# jammasave.net
KiCad netlist of a schematic drawn in EAGLE
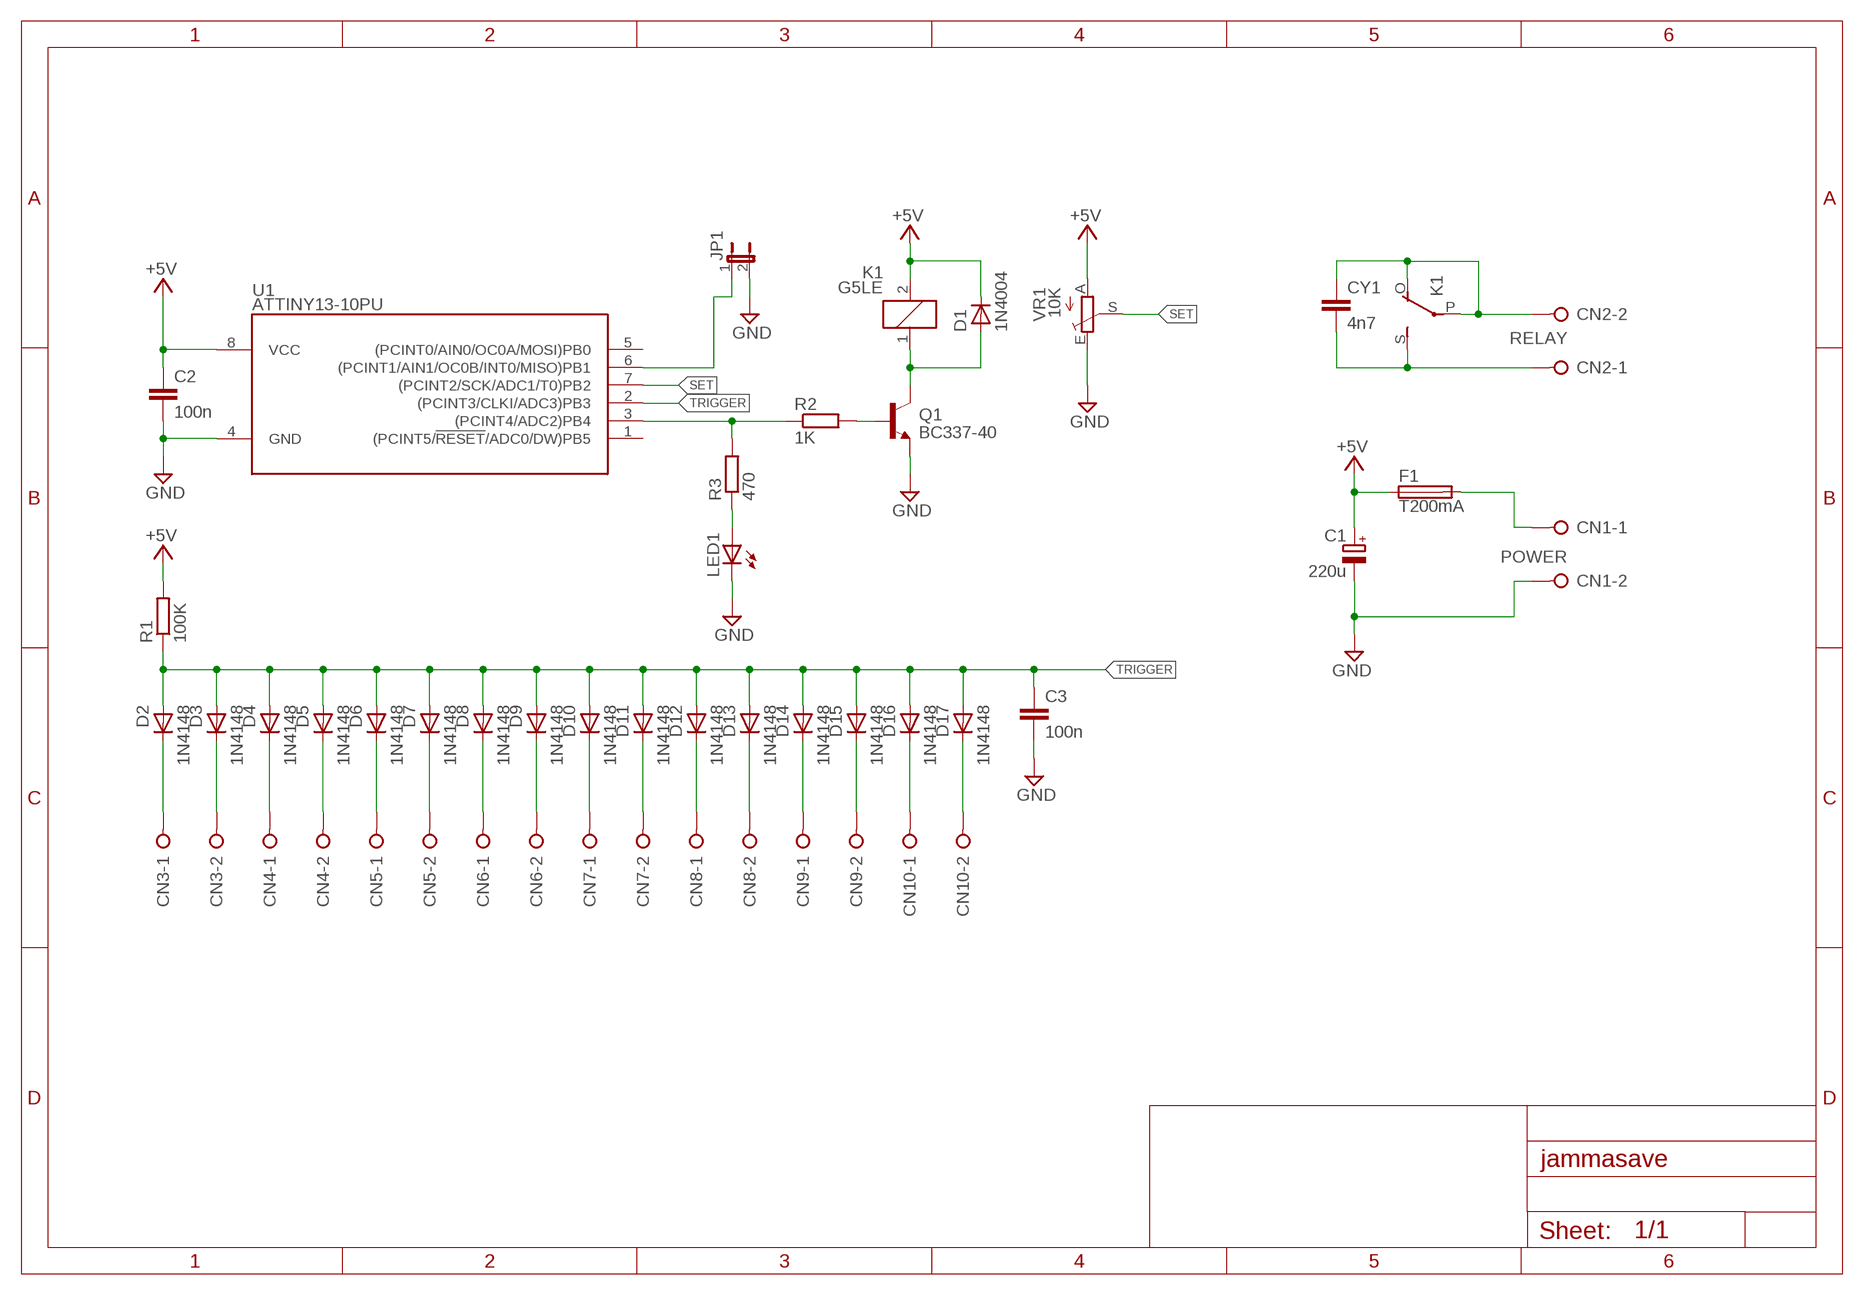
[diagram p0: schematic, sheet 1]

(export (version "E")
  (design (tool "Eeschema 10.0.6"))
  (components
    (comp (ref "C1")
      (value "220u")
      (footprint "eagle-import:E3,5-8")
      (libsource (lib "eagle-import") (part "CPOL-EUE3.5-8"))
    )
    (comp (ref "C2")
      (value "100n")
      (footprint "eagle-import:C050-035X075")
      (libsource (lib "eagle-import") (part "C-EU050-035X075"))
    )
    (comp (ref "C3")
      (value "100n")
      (footprint "eagle-import:C050-035X075")
      (libsource (lib "eagle-import") (part "C-EU050-035X075"))
    )
    (comp (ref "CN1")
      (value "POWER")
      (footprint "eagle-import:W237-132")
      (libsource (lib "eagle-import") (part "W237-02P"))
    )
    (comp (ref "CN2")
      (value "RELAY")
      (footprint "eagle-import:W237-2N")
      (libsource (lib "eagle-import") (part "W237-2N"))
    )
    (comp (ref "CN3")
      (value "W237-02P")
      (footprint "eagle-import:W237-132")
      (libsource (lib "eagle-import") (part "W237-02P"))
    )
    (comp (ref "CN4")
      (value "W237-02P")
      (footprint "eagle-import:W237-132")
      (libsource (lib "eagle-import") (part "W237-02P"))
    )
    (comp (ref "CN5")
      (value "W237-02P")
      (footprint "eagle-import:W237-132")
      (libsource (lib "eagle-import") (part "W237-02P"))
    )
    (comp (ref "CN6")
      (value "W237-02P")
      (footprint "eagle-import:W237-132")
      (libsource (lib "eagle-import") (part "W237-02P"))
    )
    (comp (ref "CN7")
      (value "W237-02P")
      (footprint "eagle-import:W237-132")
      (libsource (lib "eagle-import") (part "W237-02P"))
    )
    (comp (ref "CN8")
      (value "W237-02P")
      (footprint "eagle-import:W237-132")
      (libsource (lib "eagle-import") (part "W237-02P"))
    )
    (comp (ref "CN9")
      (value "W237-02P")
      (footprint "eagle-import:W237-132")
      (libsource (lib "eagle-import") (part "W237-02P"))
    )
    (comp (ref "CN10")
      (value "W237-02P")
      (footprint "eagle-import:W237-132")
      (libsource (lib "eagle-import") (part "W237-02P"))
    )
    (comp (ref "CY1")
      (value "4n7")
      (footprint "eagle-import:YC10B5")
      (libsource (lib "eagle-import") (part "CYYC10B5"))
    )
    (comp (ref "D1")
      (value "1N4004")
      (footprint "eagle-import:DO41-10")
      (libsource (lib "eagle-import") (part "-DIODE_?DO41-10"))
    )
    (comp (ref "D2")
      (value "1N4148")
      (footprint "eagle-import:DO35-7")
      (libsource (lib "eagle-import") (part "-DIODE_?DO35-7"))
    )
    (comp (ref "D3")
      (value "1N4148")
      (footprint "eagle-import:DO35-7")
      (libsource (lib "eagle-import") (part "-DIODE_?DO35-7"))
    )
    (comp (ref "D4")
      (value "1N4148")
      (footprint "eagle-import:DO35-7")
      (libsource (lib "eagle-import") (part "-DIODE_?DO35-7"))
    )
    (comp (ref "D5")
      (value "1N4148")
      (footprint "eagle-import:DO35-7")
      (libsource (lib "eagle-import") (part "-DIODE_?DO35-7"))
    )
    (comp (ref "D6")
      (value "1N4148")
      (footprint "eagle-import:DO35-7")
      (libsource (lib "eagle-import") (part "-DIODE_?DO35-7"))
    )
    (comp (ref "D7")
      (value "1N4148")
      (footprint "eagle-import:DO35-7")
      (libsource (lib "eagle-import") (part "-DIODE_?DO35-7"))
    )
    (comp (ref "D8")
      (value "1N4148")
      (footprint "eagle-import:DO35-7")
      (libsource (lib "eagle-import") (part "-DIODE_?DO35-7"))
    )
    (comp (ref "D9")
      (value "1N4148")
      (footprint "eagle-import:DO35-7")
      (libsource (lib "eagle-import") (part "-DIODE_?DO35-7"))
    )
    (comp (ref "D10")
      (value "1N4148")
      (footprint "eagle-import:DO35-7")
      (libsource (lib "eagle-import") (part "-DIODE_?DO35-7"))
    )
    (comp (ref "D11")
      (value "1N4148")
      (footprint "eagle-import:DO35-7")
      (libsource (lib "eagle-import") (part "-DIODE_?DO35-7"))
    )
    (comp (ref "D12")
      (value "1N4148")
      (footprint "eagle-import:DO35-7")
      (libsource (lib "eagle-import") (part "-DIODE_?DO35-7"))
    )
    (comp (ref "D13")
      (value "1N4148")
      (footprint "eagle-import:DO35-7")
      (libsource (lib "eagle-import") (part "-DIODE_?DO35-7"))
    )
    (comp (ref "D14")
      (value "1N4148")
      (footprint "eagle-import:DO35-7")
      (libsource (lib "eagle-import") (part "-DIODE_?DO35-7"))
    )
    (comp (ref "D15")
      (value "1N4148")
      (footprint "eagle-import:DO35-7")
      (libsource (lib "eagle-import") (part "-DIODE_?DO35-7"))
    )
    (comp (ref "D16")
      (value "1N4148")
      (footprint "eagle-import:DO35-7")
      (libsource (lib "eagle-import") (part "-DIODE_?DO35-7"))
    )
    (comp (ref "D17")
      (value "1N4148")
      (footprint "eagle-import:DO35-7")
      (libsource (lib "eagle-import") (part "-DIODE_?DO35-7"))
    )
    (comp (ref "F1")
      (value "T200mA")
      (footprint "eagle-import:TE5")
      (libsource (lib "eagle-import") (part "FUSETE5"))
    )
    (comp (ref "JP1")
      (value "JP1E")
      (footprint "eagle-import:JP1")
      (libsource (lib "eagle-import") (part "JP1E"))
    )
    (comp (ref "K1")
      (value "G5LE")
      (footprint "eagle-import:G5LE")
      (libsource (lib "eagle-import") (part "G5LE"))
    )
    (comp (ref "LED1")
      (value "LED3MM")
      (footprint "eagle-import:LED3MM")
      (libsource (lib "eagle-import") (part "LED3MM"))
    )
    (comp (ref "Q1")
      (value "BC337-40")
      (footprint "eagle-import:TO92-254")
      (libsource (lib "eagle-import") (part "-NPN_?TO92_254-CBE"))
    )
    (comp (ref "R1")
      (value "100K")
      (footprint "eagle-import:0207_10")
      (libsource (lib "eagle-import") (part "R-EU_0207/10"))
    )
    (comp (ref "R2")
      (value "1K")
      (footprint "eagle-import:0207_10")
      (libsource (lib "eagle-import") (part "R-EU_0207/10"))
    )
    (comp (ref "R3")
      (value "470")
      (footprint "eagle-import:0207_10")
      (libsource (lib "eagle-import") (part "R-EU_0207/10"))
    )
    (comp (ref "U1")
      (value "ATTINY13-10PU")
      (footprint "eagle-import:DIL08")
      (libsource (lib "eagle-import") (part "ATTINY13-PU10"))
    )
    (comp (ref "VR1")
      (value "10K")
      (footprint "eagle-import:CA6V")
      (libsource (lib "eagle-import") (part "TRIM_EU-CA6V"))
    )
  )
  (nets
    (net (code "1") (name "+5V") (class "Default")
      (node (ref "C1") (pin "+") (pinfunction "+_+") (pintype "passive"))
      (node (ref "C2") (pin "1") (pinfunction "1_1") (pintype "passive"))
      (node (ref "D1") (pin "K") (pinfunction "C_K") (pintype "passive"))
      (node (ref "F1") (pin "1") (pinfunction "1_1") (pintype "passive"))
      (node (ref "K1") (pin "2") (pinfunction "2_2") (pintype "passive"))
      (node (ref "R1") (pin "2") (pinfunction "2_2") (pintype "passive"))
      (node (ref "U1") (pin "8") (pinfunction "VCC_8") (pintype "power_in"))
      (node (ref "VR1") (pin "A") (pinfunction "A_A") (pintype "passive"))
    )
    (net (code "2") (name "GND") (class "Default")
      (node (ref "C1") (pin "-") (pinfunction "-_-") (pintype "passive"))
      (node (ref "C2") (pin "2") (pinfunction "2_2") (pintype "passive"))
      (node (ref "C3") (pin "2") (pinfunction "2_2") (pintype "passive"))
      (node (ref "CN1") (pin "2") (pinfunction "KL_2") (pintype "passive"))
      (node (ref "JP1") (pin "2") (pinfunction "2_2") (pintype "passive"))
      (node (ref "LED1") (pin "K") (pinfunction "C_K") (pintype "passive"))
      (node (ref "Q1") (pin "3") (pinfunction "E_3") (pintype "passive"))
      (node (ref "U1") (pin "4") (pinfunction "GND_4") (pintype "power_in"))
      (node (ref "VR1") (pin "E") (pinfunction "E_E") (pintype "passive"))
    )
    (net (code "3") (name "Net-(CN1A-KL)") (class "Default")
      (node (ref "CN1") (pin "1") (pinfunction "KL_1") (pintype "passive"))
      (node (ref "F1") (pin "2") (pinfunction "2_2") (pintype "passive"))
    )
    (net (code "4") (name "Net-(CN2A-KL)") (class "Default")
      (node (ref "CN2") (pin "1") (pinfunction "KL_1") (pintype "passive"))
      (node (ref "CY1") (pin "2") (pinfunction "2_2") (pintype "passive"))
      (node (ref "K1") (pin "S") (pinfunction "S_S") (pintype "passive"))
    )
    (net (code "5") (name "Net-(CN2B-KL)") (class "Default")
      (node (ref "CN2") (pin "2") (pinfunction "KL_2") (pintype "passive"))
      (node (ref "CY1") (pin "1") (pinfunction "1_1") (pintype "passive"))
      (node (ref "K1") (pin "O") (pinfunction "O_O") (pintype "passive"))
      (node (ref "K1") (pin "P") (pinfunction "P_P") (pintype "passive"))
    )
    (net (code "6") (name "Net-(CN3A-KL)") (class "Default")
      (node (ref "CN3") (pin "1") (pinfunction "KL_1") (pintype "passive"))
      (node (ref "D2") (pin "K") (pinfunction "C_K") (pintype "passive"))
    )
    (net (code "7") (name "Net-(CN3B-KL)") (class "Default")
      (node (ref "CN3") (pin "2") (pinfunction "KL_2") (pintype "passive"))
      (node (ref "D3") (pin "K") (pinfunction "C_K") (pintype "passive"))
    )
    (net (code "8") (name "Net-(CN4A-KL)") (class "Default")
      (node (ref "CN4") (pin "1") (pinfunction "KL_1") (pintype "passive"))
      (node (ref "D4") (pin "K") (pinfunction "C_K") (pintype "passive"))
    )
    (net (code "9") (name "Net-(CN4B-KL)") (class "Default")
      (node (ref "CN4") (pin "2") (pinfunction "KL_2") (pintype "passive"))
      (node (ref "D5") (pin "K") (pinfunction "C_K") (pintype "passive"))
    )
    (net (code "10") (name "Net-(CN5A-KL)") (class "Default")
      (node (ref "CN5") (pin "1") (pinfunction "KL_1") (pintype "passive"))
      (node (ref "D6") (pin "K") (pinfunction "C_K") (pintype "passive"))
    )
    (net (code "11") (name "Net-(CN5B-KL)") (class "Default")
      (node (ref "CN5") (pin "2") (pinfunction "KL_2") (pintype "passive"))
      (node (ref "D7") (pin "K") (pinfunction "C_K") (pintype "passive"))
    )
    (net (code "12") (name "Net-(CN6A-KL)") (class "Default")
      (node (ref "CN6") (pin "1") (pinfunction "KL_1") (pintype "passive"))
      (node (ref "D8") (pin "K") (pinfunction "C_K") (pintype "passive"))
    )
    (net (code "13") (name "Net-(CN6B-KL)") (class "Default")
      (node (ref "CN6") (pin "2") (pinfunction "KL_2") (pintype "passive"))
      (node (ref "D9") (pin "K") (pinfunction "C_K") (pintype "passive"))
    )
    (net (code "14") (name "Net-(CN7A-KL)") (class "Default")
      (node (ref "CN7") (pin "1") (pinfunction "KL_1") (pintype "passive"))
      (node (ref "D10") (pin "K") (pinfunction "C_K") (pintype "passive"))
    )
    (net (code "15") (name "Net-(CN7B-KL)") (class "Default")
      (node (ref "CN7") (pin "2") (pinfunction "KL_2") (pintype "passive"))
      (node (ref "D11") (pin "K") (pinfunction "C_K") (pintype "passive"))
    )
    (net (code "16") (name "Net-(CN8A-KL)") (class "Default")
      (node (ref "CN8") (pin "1") (pinfunction "KL_1") (pintype "passive"))
      (node (ref "D12") (pin "K") (pinfunction "C_K") (pintype "passive"))
    )
    (net (code "17") (name "Net-(CN8B-KL)") (class "Default")
      (node (ref "CN8") (pin "2") (pinfunction "KL_2") (pintype "passive"))
      (node (ref "D13") (pin "K") (pinfunction "C_K") (pintype "passive"))
    )
    (net (code "18") (name "Net-(CN9A-KL)") (class "Default")
      (node (ref "CN9") (pin "1") (pinfunction "KL_1") (pintype "passive"))
      (node (ref "D14") (pin "K") (pinfunction "C_K") (pintype "passive"))
    )
    (net (code "19") (name "Net-(CN9B-KL)") (class "Default")
      (node (ref "CN9") (pin "2") (pinfunction "KL_2") (pintype "passive"))
      (node (ref "D15") (pin "K") (pinfunction "C_K") (pintype "passive"))
    )
    (net (code "20") (name "Net-(CN10A-KL)") (class "Default")
      (node (ref "CN10") (pin "1") (pinfunction "KL_1") (pintype "passive"))
      (node (ref "D16") (pin "K") (pinfunction "C_K") (pintype "passive"))
    )
    (net (code "21") (name "Net-(CN10B-KL)") (class "Default")
      (node (ref "CN10") (pin "2") (pinfunction "KL_2") (pintype "passive"))
      (node (ref "D17") (pin "K") (pinfunction "C_K") (pintype "passive"))
    )
    (net (code "22") (name "Net-(LED1-PadA)") (class "Default")
      (node (ref "LED1") (pin "A") (pinfunction "A_A") (pintype "passive"))
      (node (ref "R3") (pin "1") (pinfunction "1_1") (pintype "passive"))
    )
    (net (code "23") (name "Net-(Q1-B)") (class "Default")
      (node (ref "Q1") (pin "2") (pinfunction "B_2") (pintype "passive"))
      (node (ref "R2") (pin "2") (pinfunction "2_2") (pintype "passive"))
    )
    (net (code "24") (name "Net-(Q1-C)") (class "Default")
      (node (ref "D1") (pin "A") (pinfunction "A_A") (pintype "passive"))
      (node (ref "K1") (pin "1") (pinfunction "1_1") (pintype "passive"))
      (node (ref "Q1") (pin "1") (pinfunction "C_1") (pintype "passive"))
    )
    (net (code "25") (name "Net-(U1-(PCINT1{slash}AIN1{slash}OC0B{slash}INT0{slash}MISO)PB1)") (class "Default")
      (node (ref "JP1") (pin "1") (pinfunction "1_1") (pintype "passive"))
      (node (ref "U1") (pin "6") (pinfunction "(PCINT1/AIN1/OC0B/INT0/MISO)PB1_6") (pintype "bidirectional"))
    )
    (net (code "26") (name "Net-(U1-(PCINT4{slash}ADC2)PB4)") (class "Default")
      (node (ref "R2") (pin "1") (pinfunction "1_1") (pintype "passive"))
      (node (ref "R3") (pin "2") (pinfunction "2_2") (pintype "passive"))
      (node (ref "U1") (pin "3") (pinfunction "(PCINT4/ADC2)PB4_3") (pintype "bidirectional"))
    )
    (net (code "27") (name "SET") (class "Default")
      (node (ref "U1") (pin "7") (pinfunction "(PCINT2/SCK/ADC1/T0)PB2_7") (pintype "bidirectional"))
      (node (ref "VR1") (pin "S") (pinfunction "S_S") (pintype "passive"))
    )
    (net (code "28") (name "TRIGGER") (class "Default")
      (node (ref "C3") (pin "1") (pinfunction "1_1") (pintype "passive"))
      (node (ref "D10") (pin "A") (pinfunction "A_A") (pintype "passive"))
      (node (ref "D11") (pin "A") (pinfunction "A_A") (pintype "passive"))
      (node (ref "D12") (pin "A") (pinfunction "A_A") (pintype "passive"))
      (node (ref "D13") (pin "A") (pinfunction "A_A") (pintype "passive"))
      (node (ref "D14") (pin "A") (pinfunction "A_A") (pintype "passive"))
      (node (ref "D15") (pin "A") (pinfunction "A_A") (pintype "passive"))
      (node (ref "D16") (pin "A") (pinfunction "A_A") (pintype "passive"))
      (node (ref "D17") (pin "A") (pinfunction "A_A") (pintype "passive"))
      (node (ref "D2") (pin "A") (pinfunction "A_A") (pintype "passive"))
      (node (ref "D3") (pin "A") (pinfunction "A_A") (pintype "passive"))
      (node (ref "D4") (pin "A") (pinfunction "A_A") (pintype "passive"))
      (node (ref "D5") (pin "A") (pinfunction "A_A") (pintype "passive"))
      (node (ref "D6") (pin "A") (pinfunction "A_A") (pintype "passive"))
      (node (ref "D7") (pin "A") (pinfunction "A_A") (pintype "passive"))
      (node (ref "D8") (pin "A") (pinfunction "A_A") (pintype "passive"))
      (node (ref "D9") (pin "A") (pinfunction "A_A") (pintype "passive"))
      (node (ref "R1") (pin "1") (pinfunction "1_1") (pintype "passive"))
      (node (ref "U1") (pin "2") (pinfunction "(PCINT3/CLKI/ADC3)PB3_2") (pintype "bidirectional"))
    )
    (net (code "29") (name "unconnected-(U1-(PCINT0{slash}AIN0{slash}OC0A{slash}MOSI)PB0-Pad5)") (class "Default")
      (node (ref "U1") (pin "5") (pinfunction "(PCINT0/AIN0/OC0A/MOSI)PB0_5") (pintype "bidirectional"))
    )
    (net (code "30") (name "unconnected-(U1-(PCINT5{slash}~{RESET}{slash}ADC0{slash}DW)PB5-Pad1)") (class "Default")
      (node (ref "U1") (pin "1") (pinfunction "(PCINT5/~{RESET}/ADC0/DW)PB5_1") (pintype "bidirectional"))
    )
  )
)
